# Nano_stepper.net
KiCad netlist of a schematic drawn in Altium Designer
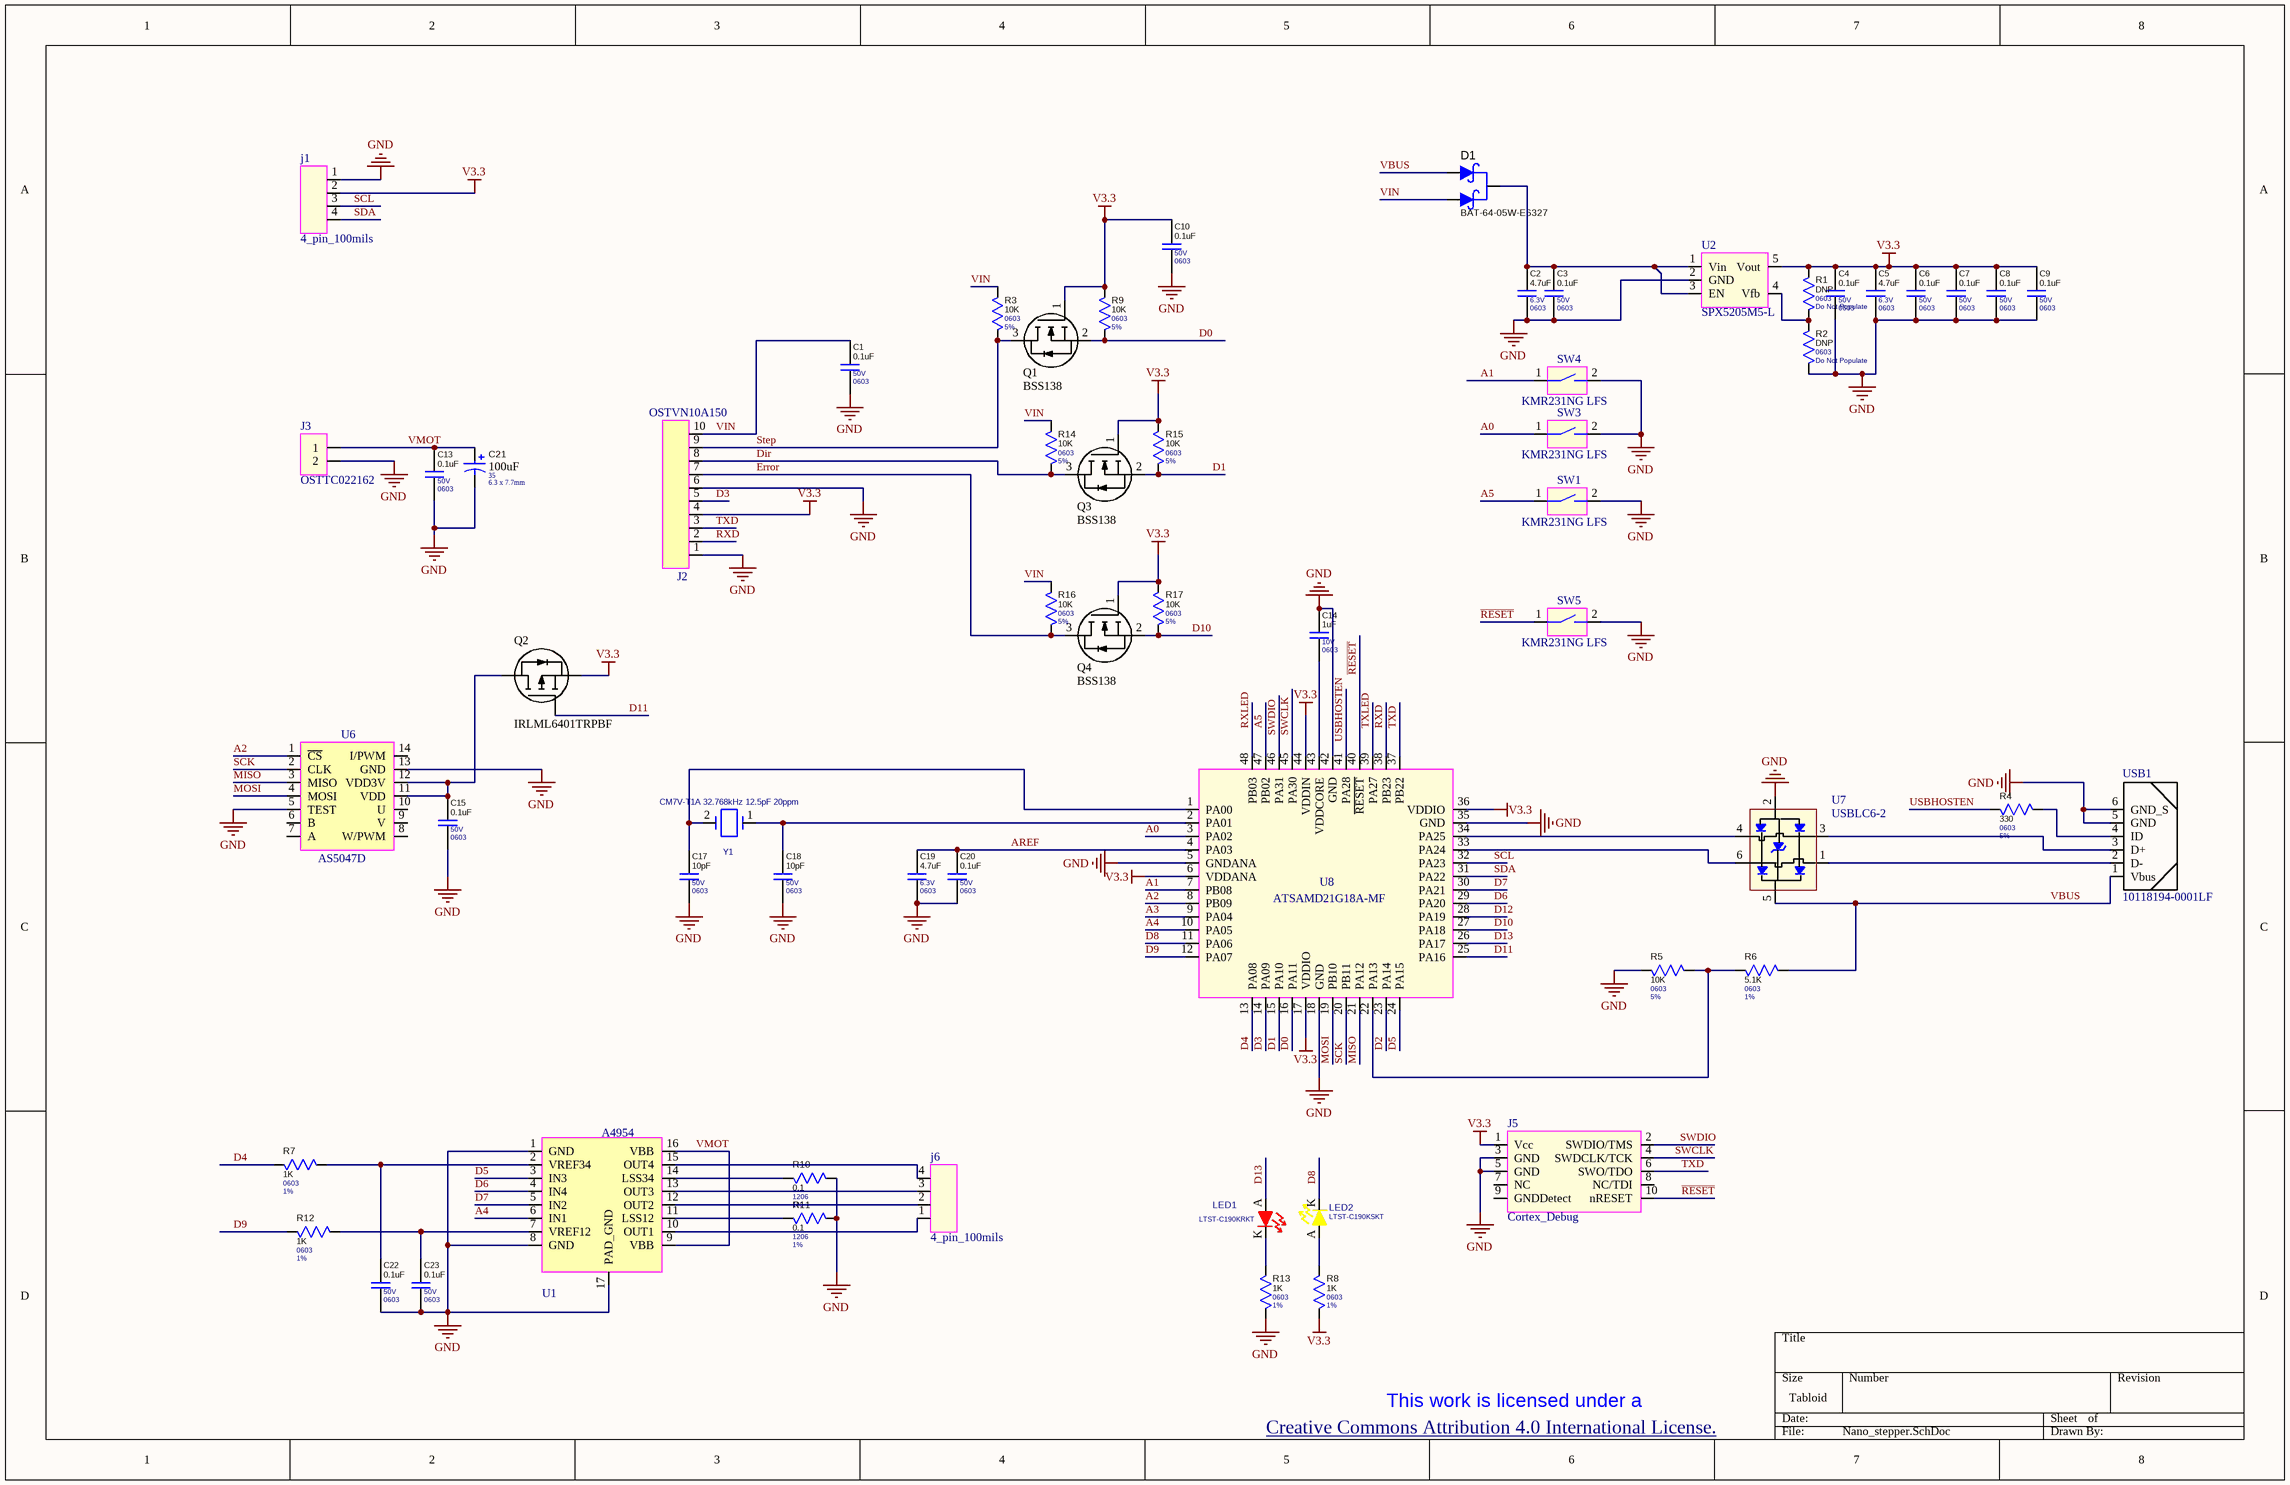
[diagram p0: Nano_stepper.SchDoc]

(export (version "E")
  (design (tool "Eeschema 10.0.6"))
  (components
    (comp (ref "C1")
      (value "0.1uF")
      (footprint "CAP_0603_H")
      (description "CAP CER 0.1UF 50V Y5V 0603")
      (fields
        (field (name "SIZE_IMPERIAL") "0603")
        (field (name "VOLTAGE_STR") "50V")
        (field (name "VOLTAGE") "50")
        (field (name "TOLERANCE") "-20%, +80%")
      )
      (libsource (lib "Misfit_library") (part "Cap"))
    )
    (comp (ref "C2")
      (value "4.7uF")
      (footprint "CAP_0603_H")
      (description "CAP 0603 CER 4.7UF 6.3V X5R 10%")
      (fields
        (field (name "SIZE_IMPERIAL") "0603")
        (field (name "VOLTAGE_STR") "6.3V")
        (field (name "VOLTAGE") "6.3")
        (field (name "TOLERANCE") "10%")
      )
      (libsource (lib "Misfit_library") (part "Cap"))
    )
    (comp (ref "C3")
      (value "0.1uF")
      (footprint "CAP_0603_H")
      (description "CAP CER 0.1UF 50V Y5V 0603")
      (fields
        (field (name "SIZE_IMPERIAL") "0603")
        (field (name "VOLTAGE_STR") "50V")
        (field (name "VOLTAGE") "50")
        (field (name "TOLERANCE") "-20%, +80%")
      )
      (libsource (lib "Misfit_library") (part "Cap"))
    )
    (comp (ref "C4")
      (value "0.1uF")
      (footprint "CAP_0603_H")
      (description "CAP CER 0.1UF 50V Y5V 0603")
      (fields
        (field (name "SIZE_IMPERIAL") "0603")
        (field (name "VOLTAGE_STR") "50V")
        (field (name "VOLTAGE") "50")
        (field (name "TOLERANCE") "-20%, +80%")
      )
      (libsource (lib "Misfit_library") (part "Cap"))
    )
    (comp (ref "C5")
      (value "4.7uF")
      (footprint "CAP_0603_H")
      (description "CAP 0603 CER 4.7UF 6.3V X5R 10%")
      (fields
        (field (name "SIZE_IMPERIAL") "0603")
        (field (name "VOLTAGE_STR") "6.3V")
        (field (name "VOLTAGE") "6.3")
        (field (name "TOLERANCE") "10%")
      )
      (libsource (lib "Misfit_library") (part "Cap"))
    )
    (comp (ref "C6")
      (value "0.1uF")
      (footprint "CAP_0603_H")
      (description "CAP CER 0.1UF 50V Y5V 0603")
      (fields
        (field (name "SIZE_IMPERIAL") "0603")
        (field (name "VOLTAGE_STR") "50V")
        (field (name "VOLTAGE") "50")
        (field (name "TOLERANCE") "-20%, +80%")
      )
      (libsource (lib "Misfit_library") (part "Cap"))
    )
    (comp (ref "C7")
      (value "0.1uF")
      (footprint "CAP_0603_H")
      (description "CAP CER 0.1UF 50V Y5V 0603")
      (fields
        (field (name "SIZE_IMPERIAL") "0603")
        (field (name "VOLTAGE_STR") "50V")
        (field (name "VOLTAGE") "50")
        (field (name "TOLERANCE") "-20%, +80%")
      )
      (libsource (lib "Misfit_library") (part "Cap"))
    )
    (comp (ref "C8")
      (value "0.1uF")
      (footprint "CAP_0603_H")
      (description "CAP CER 0.1UF 50V Y5V 0603")
      (fields
        (field (name "SIZE_IMPERIAL") "0603")
        (field (name "VOLTAGE_STR") "50V")
        (field (name "VOLTAGE") "50")
        (field (name "TOLERANCE") "-20%, +80%")
      )
      (libsource (lib "Misfit_library") (part "Cap"))
    )
    (comp (ref "C9")
      (value "0.1uF")
      (footprint "CAP_0603_H")
      (description "CAP CER 0.1UF 50V Y5V 0603")
      (fields
        (field (name "SIZE_IMPERIAL") "0603")
        (field (name "VOLTAGE_STR") "50V")
        (field (name "VOLTAGE") "50")
        (field (name "TOLERANCE") "-20%, +80%")
      )
      (libsource (lib "Misfit_library") (part "Cap"))
    )
    (comp (ref "C10")
      (value "0.1uF")
      (footprint "CAP_0603_H")
      (description "CAP CER 0.1UF 50V Y5V 0603")
      (fields
        (field (name "SIZE_IMPERIAL") "0603")
        (field (name "VOLTAGE_STR") "50V")
        (field (name "VOLTAGE") "50")
        (field (name "TOLERANCE") "-20%, +80%")
      )
      (libsource (lib "Misfit_library") (part "Cap"))
    )
    (comp (ref "C13")
      (value "0.1uF")
      (footprint "CAP_0603_H")
      (description "CAP CER 0.1UF 50V Y5V 0603")
      (fields
        (field (name "SIZE_IMPERIAL") "0603")
        (field (name "VOLTAGE_STR") "50V")
        (field (name "VOLTAGE") "50")
        (field (name "TOLERANCE") "-20%, +80%")
      )
      (libsource (lib "Misfit_library") (part "Cap"))
    )
    (comp (ref "C14")
      (value "1uF")
      (footprint "CAP_0603_H")
      (description "CAP 0603 CER 1UF 10V X5R 10%")
      (fields
        (field (name "SIZE_IMPERIAL") "0603")
        (field (name "VOLTAGE_STR") "10V")
        (field (name "VOLTAGE") "10")
        (field (name "TOLERANCE") "10 %")
      )
      (libsource (lib "Misfit_library") (part "Cap"))
    )
    (comp (ref "C15")
      (value "0.1uF")
      (footprint "CAP_0603_H")
      (description "CAP CER 0.1UF 50V Y5V 0603")
      (fields
        (field (name "SIZE_IMPERIAL") "0603")
        (field (name "VOLTAGE_STR") "50V")
        (field (name "VOLTAGE") "50")
        (field (name "TOLERANCE") "-20%, +80%")
      )
      (libsource (lib "Misfit_library") (part "Cap"))
    )
    (comp (ref "C17")
      (value "10pF")
      (footprint "CAP_0603_H")
      (description "CAP 0603 CER 10PF 50V C0G 5%")
      (fields
        (field (name "SIZE_IMPERIAL") "0603")
        (field (name "VOLTAGE_STR") "50V")
        (field (name "VOLTAGE") "50")
        (field (name "TOLERANCE") "5 %")
      )
      (libsource (lib "Misfit_library") (part "Cap"))
    )
    (comp (ref "C18")
      (value "10pF")
      (footprint "CAP_0603_H")
      (description "CAP 0603 CER 10PF 50V C0G 5%")
      (fields
        (field (name "SIZE_IMPERIAL") "0603")
        (field (name "VOLTAGE_STR") "50V")
        (field (name "VOLTAGE") "50")
        (field (name "TOLERANCE") "5 %")
      )
      (libsource (lib "Misfit_library") (part "Cap"))
    )
    (comp (ref "C19")
      (value "4.7uF")
      (footprint "CAP_0603_H")
      (description "CAP 0603 CER 4.7UF 6.3V X5R 10%")
      (fields
        (field (name "SIZE_IMPERIAL") "0603")
        (field (name "VOLTAGE_STR") "6.3V")
        (field (name "VOLTAGE") "6.3")
        (field (name "TOLERANCE") "10%")
      )
      (libsource (lib "Misfit_library") (part "Cap"))
    )
    (comp (ref "C20")
      (value "0.1uF")
      (footprint "CAP_0603_H")
      (description "CAP CER 0.1UF 50V Y5V 0603")
      (fields
        (field (name "SIZE_IMPERIAL") "0603")
        (field (name "VOLTAGE_STR") "50V")
        (field (name "VOLTAGE") "50")
        (field (name "TOLERANCE") "-20%, +80%")
      )
      (libsource (lib "Misfit_library") (part "Cap"))
    )
    (comp (ref "C21")
      (value "100uF")
      (footprint "UWT1V101MCL1GS")
      (description "100uF 35V SMD")
      (fields
        (field (name "SIZE") "6.3 x 7.7mm")
        (field (name "VOLTAGE") "35")
        (field (name "TOLERANCE") "20%")
        (field (name "MANUFACTURER_PART_NUMBER") "UWT1V101MCL1GS")
      )
      (libsource (lib "Misfit_library") (part "CAP_POL"))
    )
    (comp (ref "C22")
      (value "0.1uF")
      (footprint "CAP_0603_H")
      (description "CAP CER 0.1UF 50V Y5V 0603")
      (fields
        (field (name "SIZE_IMPERIAL") "0603")
        (field (name "VOLTAGE_STR") "50V")
        (field (name "VOLTAGE") "50")
        (field (name "TOLERANCE") "-20%, +80%")
      )
      (libsource (lib "Misfit_library") (part "Cap"))
    )
    (comp (ref "C23")
      (value "0.1uF")
      (footprint "CAP_0603_H")
      (description "CAP CER 0.1UF 50V Y5V 0603")
      (fields
        (field (name "SIZE_IMPERIAL") "0603")
        (field (name "VOLTAGE_STR") "50V")
        (field (name "VOLTAGE") "50")
        (field (name "TOLERANCE") "-20%, +80%")
      )
      (libsource (lib "Misfit_library") (part "Cap"))
    )
    (comp (ref "D1")
      (value "BAT-64-05W-E6327")
      (footprint "BAT-64-05W-E6327")
      (description "DIODE SCHOTTKY 40V SOT-323 250mA")
      (fields
        (field (name "MANUFACTURER_PART_NUMBER") "BAT 64-05W H6327")
        (field (name "MANUFACTURER") "Infineon Technologies")
      )
      (libsource (lib "Misfit_library") (part "BAT-64-05W-E6327"))
    )
    (comp (ref "j1")
      (value "4_pin_100mils")
      (footprint "4_pin_100mils")
      (fields (field (name "MANUFACTURER") "none") (field (name "VOLTAGE") "0"))
      (libsource (lib "Misfit_library") (part "4_pin_100mils"))
    )
    (comp (ref "J2")
      (value "OSTVN10A150")
      (footprint "OSTVN10A150")
      (description "CONN TERM BLOCK 2.54MM 10POS PCB")
      (fields
        (field (name "MANUFACTURER") "On Shore Technology Inc.")
        (field (name "VENDOR_PART_NUMBER") "ED10567-ND")
      )
      (libsource (lib "Misfit_library") (part "OSTVN10A150"))
    )
    (comp (ref "J3")
      (value "OSTTC022162")
      (footprint "OSTTC022162")
      (description "TERM BLOCK 5.08MM VERT 2POS PCB")
      (fields
        (field (name "MANUFACTURER") "On Shore Technology Inc")
        (field (name "VENDOR_PART_NUMBER") "ED2609-ND")
      )
      (libsource (lib "Misfit_library") (part "OSTTC022162"))
    )
    (comp (ref "J5")
      (value "Cortex_Debug")
      (footprint "FTSH-105-01-L-D")
      (description "CONN HEADER 10POS DUAL .05&quot; T/H")
      (fields
        (field (name "MANUFACTURER_PART_NUMBER") "FTSH-105-01-L-D")
        (field (name "MANUFACTURER") "Samtec Inc")
      )
      (libsource (lib "Misfit_library") (part "Cortex_Debug"))
    )
    (comp (ref "j6")
      (value "4_pin_100mils")
      (footprint "4_pin_100mils")
      (fields (field (name "MANUFACTURER") "none") (field (name "VOLTAGE") "0"))
      (libsource (lib "") (part "4_pin_100mils_1"))
    )
    (comp (ref "LED1")
      (value "LTST-C190KRKT")
      (footprint "LTST-C190KRKT")
      (description "LED SUPER RED CLEAR 0603 SMD 20mA Vf=2V")
      (fields (field (name "MANUFACTURER") "Lite-On Inc") (field (name "VENDOR_PART_NUMBER") "160-1436-1-ND"))
      (libsource (lib "Misfit_library") (part "RED_LED"))
    )
    (comp (ref "LED2")
      (value "LTST-C190KSKT")
      (footprint "LTST-C190KSKT")
      (description "LED YELLOW CLEAR 0603 SMD")
      (fields (field (name "MANUFACTURER") "Lite-On Inc") (field (name "VENDOR_PART_NUMBER") "160-1437-6-ND"))
      (libsource (lib "Misfit_library") (part "LTST-C190KSKT"))
    )
    (comp (ref "Q1")
      (value "BSS138")
      (footprint "BSS138")
      (fields (field (name "VOLTAGE") "0"))
      (libsource (lib "Misfit_library") (part "BSS138"))
    )
    (comp (ref "Q2")
      (value "IRLML6401TRPBF")
      (footprint "IRLML6401TRPBF_M")
      (description "MOSFET P-CH 12V 4.3A SOT-23")
      (fields
        (field (name "MANUFACTURER") "International Rectifier")
        (field (name "MISFIT PART NUMBER") "00013-209-00061")
      )
      (libsource (lib "Misfit_library") (part "IRLML6401TRPBF"))
    )
    (comp (ref "Q3")
      (value "BSS138")
      (footprint "BSS138")
      (fields (field (name "VOLTAGE") "0"))
      (libsource (lib "Misfit_library") (part "BSS138"))
    )
    (comp (ref "Q4")
      (value "BSS138")
      (footprint "BSS138")
      (fields (field (name "VOLTAGE") "0"))
      (libsource (lib "Misfit_library") (part "BSS138"))
    )
    (comp (ref "R1")
      (value "DNP")
      (footprint "RES_0603_H")
      (fields
        (field (name "SIZE_IMPERIAL") "0603")
        (field (name "TOLERANCE") "Do Not Populate")
        (field (name "MISFIT PART NUMBER") "00015-126-00006")
        (field (name "OLD PART NUMBER") "4530-0101-00")
        (field (name "VENDOR_PART_NUMBER") "P0.0GTR-ND")
      )
      (libsource (lib "Misfit_library") (part "resistor"))
    )
    (comp (ref "R2")
      (value "DNP")
      (footprint "RES_0603_H")
      (fields
        (field (name "SIZE_IMPERIAL") "0603")
        (field (name "TOLERANCE") "Do Not Populate")
        (field (name "MISFIT PART NUMBER") "00015-126-00006")
        (field (name "OLD PART NUMBER") "4530-0101-00")
        (field (name "VENDOR_PART_NUMBER") "P0.0GTR-ND")
      )
      (libsource (lib "Misfit_library") (part "resistor"))
    )
    (comp (ref "R3")
      (value "10K")
      (footprint "RES_0603_H")
      (description "RES 0603 TKF 10K 5% 1/10W")
      (fields
        (field (name "SIZE_IMPERIAL") "0603")
        (field (name "TOLERANCE") "5%")
        (field (name "MANUFACTURER_PART_NUMBER") "RC0603JR-0710KL")
        (field (name "MANUFACTURER") "Yageo")
      )
      (libsource (lib "Misfit_library") (part "resistor"))
    )
    (comp (ref "R4")
      (value "330")
      (footprint "RES_0603_H")
      (description "RES 0603 TKF 330R 5% 1/10W")
      (fields
        (field (name "SIZE_IMPERIAL") "0603")
        (field (name "TOLERANCE") "5%")
        (field (name "MANUFACTURER_PART_NUMBER") "RC0603JR-07330RL")
        (field (name "MANUFACTURER") "Yageo")
      )
      (libsource (lib "Misfit_library") (part "resistor"))
    )
    (comp (ref "R5")
      (value "10K")
      (footprint "RES_0603_H")
      (description "RES 0603 TKF 10K 5% 1/10W")
      (fields
        (field (name "SIZE_IMPERIAL") "0603")
        (field (name "TOLERANCE") "5%")
        (field (name "MANUFACTURER_PART_NUMBER") "RC0603JR-0710KL")
        (field (name "MANUFACTURER") "Yageo")
      )
      (libsource (lib "Misfit_library") (part "resistor"))
    )
    (comp (ref "R6")
      (value "5.1K")
      (footprint "RES_0603_H")
      (description "RES 0603 TKF 5.1K 1% 1/10W")
      (fields
        (field (name "SIZE_IMPERIAL") "0603")
        (field (name "TOLERANCE") "1%")
        (field (name "MANUFACTURER_PART_NUMBER") "CRCW06035K10FKEA")
        (field (name "MANUFACTURER") "Vishay/Dale")
      )
      (libsource (lib "Misfit_library") (part "resistor"))
    )
    (comp (ref "R7")
      (value "1K")
      (footprint "RES_0603_H")
      (description "RES 0603 TKF 1K 1% 1/10W")
      (fields
        (field (name "SIZE_IMPERIAL") "0603")
        (field (name "TOLERANCE") "1%")
        (field (name "MANUFACTURER_PART_NUMBER") "CRCW06031K00FKEAHP")
        (field (name "MANUFACTURER") "Vishay/Dale")
      )
      (libsource (lib "Misfit_library") (part "resistor"))
    )
    (comp (ref "R8")
      (value "1K")
      (footprint "RES_0603_H")
      (description "RES 0603 TKF 1K 1% 1/10W")
      (fields
        (field (name "SIZE_IMPERIAL") "0603")
        (field (name "TOLERANCE") "1%")
        (field (name "MANUFACTURER_PART_NUMBER") "CRCW06031K00FKEAHP")
        (field (name "MANUFACTURER") "Vishay/Dale")
      )
      (libsource (lib "Misfit_library") (part "resistor"))
    )
    (comp (ref "R9")
      (value "10K")
      (footprint "RES_0603_H")
      (description "RES 0603 TKF 10K 5% 1/10W")
      (fields
        (field (name "SIZE_IMPERIAL") "0603")
        (field (name "TOLERANCE") "5%")
        (field (name "MANUFACTURER_PART_NUMBER") "RC0603JR-0710KL")
        (field (name "MANUFACTURER") "Yageo")
      )
      (libsource (lib "Misfit_library") (part "resistor"))
    )
    (comp (ref "R10")
      (value "0.1")
      (footprint "RES_1206_H")
      (description "RES 0.2 OHM 0.25W 1% 1206 SMD")
      (fields
        (field (name "SIZE_IMPERIAL") "1206")
        (field (name "TOLERANCE") "1%")
        (field (name "MANUFACTURER_PART_NUMBER") "PT1206FR-070R2L")
        (field (name "MANUFACTURER") "Yageo")
      )
      (libsource (lib "Misfit_library") (part "resistor"))
    )
    (comp (ref "R11")
      (value "0.1")
      (footprint "RES_1206_H")
      (description "RES 0.2 OHM 0.25W 1% 1206 SMD")
      (fields
        (field (name "SIZE_IMPERIAL") "1206")
        (field (name "TOLERANCE") "1%")
        (field (name "MANUFACTURER_PART_NUMBER") "PT1206FR-070R2L")
        (field (name "MANUFACTURER") "Yageo")
      )
      (libsource (lib "Misfit_library") (part "resistor"))
    )
    (comp (ref "R12")
      (value "1K")
      (footprint "RES_0603_H")
      (description "RES 0603 TKF 1K 1% 1/10W")
      (fields
        (field (name "SIZE_IMPERIAL") "0603")
        (field (name "TOLERANCE") "1%")
        (field (name "MANUFACTURER_PART_NUMBER") "CRCW06031K00FKEAHP")
        (field (name "MANUFACTURER") "Vishay/Dale")
      )
      (libsource (lib "Misfit_library") (part "resistor"))
    )
    (comp (ref "R13")
      (value "1K")
      (footprint "RES_0603_H")
      (description "RES 0603 TKF 1K 1% 1/10W")
      (fields
        (field (name "SIZE_IMPERIAL") "0603")
        (field (name "TOLERANCE") "1%")
        (field (name "MANUFACTURER_PART_NUMBER") "CRCW06031K00FKEAHP")
        (field (name "MANUFACTURER") "Vishay/Dale")
      )
      (libsource (lib "Misfit_library") (part "resistor"))
    )
    (comp (ref "R14")
      (value "10K")
      (footprint "RES_0603_H")
      (description "RES 0603 TKF 10K 5% 1/10W")
      (fields
        (field (name "SIZE_IMPERIAL") "0603")
        (field (name "TOLERANCE") "5%")
        (field (name "MANUFACTURER_PART_NUMBER") "RC0603JR-0710KL")
        (field (name "MANUFACTURER") "Yageo")
      )
      (libsource (lib "Misfit_library") (part "resistor"))
    )
    (comp (ref "R15")
      (value "10K")
      (footprint "RES_0603_H")
      (description "RES 0603 TKF 10K 5% 1/10W")
      (fields
        (field (name "SIZE_IMPERIAL") "0603")
        (field (name "TOLERANCE") "5%")
        (field (name "MANUFACTURER_PART_NUMBER") "RC0603JR-0710KL")
        (field (name "MANUFACTURER") "Yageo")
      )
      (libsource (lib "Misfit_library") (part "resistor"))
    )
    (comp (ref "R16")
      (value "10K")
      (footprint "RES_0603_H")
      (description "RES 0603 TKF 10K 5% 1/10W")
      (fields
        (field (name "SIZE_IMPERIAL") "0603")
        (field (name "TOLERANCE") "5%")
        (field (name "MANUFACTURER_PART_NUMBER") "RC0603JR-0710KL")
        (field (name "MANUFACTURER") "Yageo")
      )
      (libsource (lib "Misfit_library") (part "resistor"))
    )
    (comp (ref "R17")
      (value "10K")
      (footprint "RES_0603_H")
      (description "RES 0603 TKF 10K 5% 1/10W")
      (fields
        (field (name "SIZE_IMPERIAL") "0603")
        (field (name "TOLERANCE") "5%")
        (field (name "MANUFACTURER_PART_NUMBER") "RC0603JR-0710KL")
        (field (name "MANUFACTURER") "Yageo")
      )
      (libsource (lib "Misfit_library") (part "resistor"))
    )
    (comp (ref "SW1")
      (value "KMR231NG LFS")
      (footprint "KMR231NG_LFS")
      (fields (field (name "VOLTAGE") "0"))
      (libsource (lib "Misfit_library") (part "KMR231NG_LFS"))
    )
    (comp (ref "SW3")
      (value "KMR231NG LFS")
      (footprint "KMR231NG_LFS")
      (fields (field (name "VOLTAGE") "0"))
      (libsource (lib "Misfit_library") (part "KMR231NG_LFS"))
    )
    (comp (ref "SW4")
      (value "KMR231NG LFS")
      (footprint "KMR231NG_LFS")
      (fields (field (name "VOLTAGE") "0"))
      (libsource (lib "Misfit_library") (part "KMR231NG_LFS"))
    )
    (comp (ref "SW5")
      (value "KMR231NG LFS")
      (footprint "KMR231NG_LFS")
      (fields (field (name "VOLTAGE") "0"))
      (libsource (lib "Misfit_library") (part "KMR231NG_LFS"))
    )
    (comp (ref "U1")
      (value "A4954")
      (footprint "A4954")
      (fields (field (name "VOLTAGE") "0"))
      (libsource (lib "Misfit_library") (part "A4954"))
    )
    (comp (ref "U2")
      (value "SPX5205M5-L")
      (footprint "SPX5205M5-L")
      (description "IC REG LDO ADJ 150MA LN SOT23-5")
      (fields
        (field (name "MANUFACTURER") "Exar Corporation")
        (field (name "MISFIT PART NUMBER") "00012-001-42775")
      )
      (libsource (lib "Misfit_library") (part "SPX5205M5-L"))
    )
    (comp (ref "U6")
      (value "AS5047D")
      (footprint "AS5047D")
      (fields (field (name "VOLTAGE") "0"))
      (libsource (lib "Misfit_library") (part "AS5047D"))
    )
    (comp (ref "U7")
      (value "USBLC6-2")
      (footprint "USBLC6-2SC6")
      (description "TVS Diode Arrays ESD Protection Low Cap")
      (fields
        (field (name "MANUFACTURER_PART_NUMBER") "USBLC6-2SC6")
        (field (name "MANUFACTURER") "STMicroelectronics")
      )
      (libsource (lib "Misfit_library") (part "USBLC6-2SC6"))
    )
    (comp (ref "U8")
      (value "ATSAMD21G18A-MF")
      (footprint "ATSAMD21G18A-MF")
      (libsource (lib "Misfit_library") (part "ATSAMD21G18A-MF"))
    )
    (comp (ref "USB1")
      (value "10118194-0001LF")
      (footprint "10118194-0001LF")
      (description "Connector Receptacle USB - micro B 2.0 5 Position Surface Mount, Right Angle, Horizontal")
      (fields (field (name "MANUFACTURER") "FCI") (field (name "VENDOR_PART_NUMBER") "609-4618-6-ND"))
      (libsource (lib "Misfit_library") (part "10118194-0001LF"))
    )
    (comp (ref "Y1")
      (value "CM7V-T1A 32.768kHz 12.5pF 20ppm")
      (footprint "FC-135-32.7680KA-A3")
      (description "CRYSTAL 32.7680KHZ 12.5PF SMD")
      (fields
        (field (name "MANUFACTURER") "Micro Crystal")
        (field (name "MISFIT PART NUMBER") "00012-001-47041")
      )
      (libsource (lib "Misfit_library") (part "CRYSTAL"))
    )
  )
  (nets
    (net (code "1") (name "/A0") (class "Default")
      (node (ref "SW3") (pin "1") (pintype "passive"))
      (node (ref "U8") (pin "3") (pinfunction "PA02_3") (pintype "passive"))
    )
    (net (code "2") (name "/A1") (class "Default")
      (node (ref "SW4") (pin "1") (pintype "passive"))
      (node (ref "U8") (pin "7") (pinfunction "PB08_7") (pintype "passive"))
    )
    (net (code "3") (name "/A2") (class "Default")
      (node (ref "U6") (pin "1") (pinfunction "CS_1") (pintype "passive"))
      (node (ref "U8") (pin "8") (pinfunction "PB09_8") (pintype "passive"))
    )
    (net (code "4") (name "/A3") (class "Default")
      (node (ref "U8") (pin "9") (pinfunction "PA04_9") (pintype "passive"))
    )
    (net (code "5") (name "/A4") (class "Default")
      (node (ref "U1") (pin "6") (pinfunction "IN1_6") (pintype "passive"))
      (node (ref "U8") (pin "10") (pinfunction "PA05_10") (pintype "passive"))
    )
    (net (code "6") (name "/A5") (class "Default")
      (node (ref "SW1") (pin "1") (pintype "passive"))
      (node (ref "U8") (pin "47") (pinfunction "PB02_47") (pintype "passive"))
    )
    (net (code "7") (name "/AREF") (class "Default")
      (node (ref "C19") (pin "1") (pintype "passive"))
      (node (ref "C20") (pin "1") (pintype "passive"))
      (node (ref "U8") (pin "4") (pinfunction "PA03_4") (pintype "passive"))
    )
    (net (code "8") (name "/D0") (class "Default")
      (node (ref "Q1") (pin "2") (pintype "passive"))
      (node (ref "R9") (pin "1") (pintype "passive"))
      (node (ref "U8") (pin "16") (pinfunction "PA11_16") (pintype "passive"))
    )
    (net (code "9") (name "/D1") (class "Default")
      (node (ref "Q3") (pin "2") (pintype "passive"))
      (node (ref "R15") (pin "1") (pintype "passive"))
      (node (ref "U8") (pin "15") (pinfunction "PA10_15") (pintype "passive"))
    )
    (net (code "10") (name "/D2") (class "Default")
      (node (ref "U8") (pin "23") (pinfunction "PA14_23") (pintype "passive"))
    )
    (net (code "11") (name "/D3") (class "Default")
      (node (ref "J2") (pin "5") (pintype "passive"))
      (node (ref "U8") (pin "14") (pinfunction "PA09_14") (pintype "passive"))
    )
    (net (code "12") (name "/D4") (class "Default")
      (node (ref "R7") (pin "1") (pintype "passive"))
      (node (ref "U8") (pin "13") (pinfunction "PA08_13") (pintype "passive"))
    )
    (net (code "13") (name "/D5") (class "Default")
      (node (ref "U1") (pin "3") (pinfunction "IN3_3") (pintype "passive"))
      (node (ref "U8") (pin "24") (pinfunction "PA15_24") (pintype "passive"))
    )
    (net (code "14") (name "/D6") (class "Default")
      (node (ref "U1") (pin "4") (pinfunction "IN4_4") (pintype "passive"))
      (node (ref "U8") (pin "29") (pinfunction "PA20_29") (pintype "passive"))
    )
    (net (code "15") (name "/D7") (class "Default")
      (node (ref "U1") (pin "5") (pinfunction "IN2_5") (pintype "passive"))
      (node (ref "U8") (pin "30") (pinfunction "PA21_30") (pintype "passive"))
    )
    (net (code "16") (name "/D8") (class "Default")
      (node (ref "LED2") (pin "K") (pinfunction "K_K") (pintype "passive"))
      (node (ref "U8") (pin "11") (pinfunction "PA06_11") (pintype "passive"))
    )
    (net (code "17") (name "/D9") (class "Default")
      (node (ref "R12") (pin "1") (pintype "passive"))
      (node (ref "U8") (pin "12") (pinfunction "PA07_12") (pintype "passive"))
    )
    (net (code "18") (name "/D10") (class "Default")
      (node (ref "Q4") (pin "2") (pintype "passive"))
      (node (ref "R17") (pin "1") (pintype "passive"))
      (node (ref "U8") (pin "27") (pinfunction "PA18_27") (pintype "passive"))
    )
    (net (code "19") (name "/D11") (class "Default")
      (node (ref "Q2") (pin "1") (pintype "passive"))
      (node (ref "U8") (pin "25") (pinfunction "PA16_25") (pintype "passive"))
    )
    (net (code "20") (name "/D12") (class "Default")
      (node (ref "U8") (pin "28") (pinfunction "PA19_28") (pintype "passive"))
    )
    (net (code "21") (name "/D13") (class "Default")
      (node (ref "LED1") (pin "A") (pinfunction "A_A") (pintype "passive"))
      (node (ref "U8") (pin "26") (pinfunction "PA17_26") (pintype "passive"))
    )
    (net (code "22") (name "/Dir") (class "Default")
      (node (ref "J2") (pin "8") (pintype "passive"))
      (node (ref "Q3") (pin "3") (pintype "passive"))
      (node (ref "R14") (pin "1") (pintype "passive"))
    )
    (net (code "23") (name "/Error") (class "Default")
      (node (ref "J2") (pin "7") (pintype "passive"))
      (node (ref "Q4") (pin "3") (pintype "passive"))
      (node (ref "R16") (pin "1") (pintype "passive"))
    )
    (net (code "24") (name "/MISO") (class "Default")
      (node (ref "U6") (pin "3") (pinfunction "MISO_3") (pintype "passive"))
      (node (ref "U8") (pin "21") (pinfunction "PA12_21") (pintype "passive"))
    )
    (net (code "25") (name "/MOSI") (class "Default")
      (node (ref "U6") (pin "4") (pinfunction "MOSI_4") (pintype "passive"))
      (node (ref "U8") (pin "19") (pinfunction "PB10_19") (pintype "passive"))
    )
    (net (code "26") (name "/RESET") (class "Default")
      (node (ref "J5") (pin "10") (pinfunction "nRESET_10") (pintype "passive"))
      (node (ref "SW5") (pin "1") (pintype "passive"))
      (node (ref "U8") (pin "40") (pinfunction "RESET_40") (pintype "passive"))
    )
    (net (code "27") (name "/RXD") (class "Default")
      (node (ref "J2") (pin "2") (pintype "passive"))
      (node (ref "U8") (pin "38") (pinfunction "PB23_38") (pintype "passive"))
    )
    (net (code "28") (name "/RXLED") (class "Default")
      (node (ref "U8") (pin "48") (pinfunction "PB03_48") (pintype "passive"))
    )
    (net (code "29") (name "/SCK") (class "Default")
      (node (ref "U6") (pin "2") (pinfunction "CLK_2") (pintype "passive"))
      (node (ref "U8") (pin "20") (pinfunction "PB11_20") (pintype "passive"))
    )
    (net (code "30") (name "/SCL") (class "Default")
      (node (ref "U8") (pin "32") (pinfunction "PA23_32") (pintype "passive"))
      (node (ref "j1") (pin "3") (pinfunction "3_3") (pintype "passive"))
    )
    (net (code "31") (name "/SDA") (class "Default")
      (node (ref "U8") (pin "31") (pinfunction "PA22_31") (pintype "passive"))
      (node (ref "j1") (pin "4") (pinfunction "4_4") (pintype "passive"))
    )
    (net (code "32") (name "/SWCLK") (class "Default")
      (node (ref "J5") (pin "4") (pinfunction "SWDCLK/TCK_4") (pintype "passive"))
      (node (ref "U8") (pin "45") (pinfunction "PA30_45") (pintype "passive"))
    )
    (net (code "33") (name "/SWDIO") (class "Default")
      (node (ref "J5") (pin "2") (pinfunction "SWDIO/TMS_2") (pintype "passive"))
      (node (ref "U8") (pin "46") (pinfunction "PA31_46") (pintype "passive"))
    )
    (net (code "34") (name "/Step") (class "Default")
      (node (ref "J2") (pin "9") (pintype "passive"))
      (node (ref "Q1") (pin "3") (pintype "passive"))
      (node (ref "R3") (pin "1") (pintype "passive"))
    )
    (net (code "35") (name "/TXD") (class "Default")
      (node (ref "J2") (pin "3") (pintype "passive"))
      (node (ref "J5") (pin "6") (pinfunction "SWO/TDO_6") (pintype "passive"))
      (node (ref "U8") (pin "37") (pinfunction "PB22_37") (pintype "passive"))
    )
    (net (code "36") (name "/TXLED") (class "Default")
      (node (ref "U8") (pin "39") (pinfunction "PA27_39") (pintype "passive"))
    )
    (net (code "37") (name "/USBHOSTEN") (class "Default")
      (node (ref "R4") (pin "1") (pintype "passive"))
      (node (ref "U8") (pin "41") (pinfunction "PA28_41") (pintype "passive"))
    )
    (net (code "38") (name "/VBUS") (class "Default")
      (node (ref "D1") (pin "1") (pintype "passive"))
      (node (ref "R6") (pin "2") (pintype "passive"))
      (node (ref "U7") (pin "5") (pinfunction "VBUS_5") (pintype "passive"))
      (node (ref "USB1") (pin "1") (pinfunction "Vbus_1") (pintype "passive"))
    )
    (net (code "39") (name "/VIN") (class "Default")
      (node (ref "C1") (pin "1") (pintype "passive"))
      (node (ref "D1") (pin "2") (pintype "passive"))
      (node (ref "J2") (pin "10") (pintype "passive"))
      (node (ref "R14") (pin "2") (pintype "passive"))
      (node (ref "R16") (pin "2") (pintype "passive"))
      (node (ref "R3") (pin "2") (pintype "passive"))
    )
    (net (code "40") (name "/VMOT") (class "Default")
      (node (ref "C13") (pin "1") (pintype "passive"))
      (node (ref "C21") (pin "1") (pinfunction "Pos_1") (pintype "passive"))
      (node (ref "J3") (pin "1") (pinfunction "1_1") (pintype "passive"))
      (node (ref "U1") (pin "16") (pinfunction "VBB_16") (pintype "passive"))
      (node (ref "U1") (pin "9") (pinfunction "VBB_9") (pintype "passive"))
    )
    (net (code "41") (name "GND") (class "Default")
      (node (ref "C1") (pin "2") (pintype "passive"))
      (node (ref "C10") (pin "2") (pintype "passive"))
      (node (ref "C13") (pin "2") (pintype "passive"))
      (node (ref "C14") (pin "1") (pintype "passive"))
      (node (ref "C15") (pin "2") (pintype "passive"))
      (node (ref "C17") (pin "2") (pintype "passive"))
      (node (ref "C18") (pin "2") (pintype "passive"))
      (node (ref "C19") (pin "2") (pintype "passive"))
      (node (ref "C2") (pin "2") (pintype "passive"))
      (node (ref "C20") (pin "2") (pintype "passive"))
      (node (ref "C21") (pin "2") (pinfunction "Neg_2") (pintype "passive"))
      (node (ref "C22") (pin "2") (pintype "passive"))
      (node (ref "C23") (pin "2") (pintype "passive"))
      (node (ref "C3") (pin "2") (pintype "passive"))
      (node (ref "C4") (pin "2") (pintype "passive"))
      (node (ref "C5") (pin "2") (pintype "passive"))
      (node (ref "C6") (pin "2") (pintype "passive"))
      (node (ref "C7") (pin "2") (pintype "passive"))
      (node (ref "C8") (pin "2") (pintype "passive"))
      (node (ref "C9") (pin "2") (pintype "passive"))
      (node (ref "J2") (pin "1") (pintype "passive"))
      (node (ref "J2") (pin "6") (pintype "passive"))
      (node (ref "J3") (pin "2") (pinfunction "2_2") (pintype "passive"))
      (node (ref "J5") (pin "3") (pinfunction "GND_3") (pintype "passive"))
      (node (ref "J5") (pin "5") (pinfunction "GND_5") (pintype "passive"))
      (node (ref "R10") (pin "2") (pintype "passive"))
      (node (ref "R11") (pin "2") (pintype "passive"))
      (node (ref "R13") (pin "2") (pintype "passive"))
      (node (ref "R2") (pin "1") (pintype "passive"))
      (node (ref "R5") (pin "1") (pintype "passive"))
      (node (ref "SW1") (pin "2") (pintype "passive"))
      (node (ref "SW3") (pin "2") (pintype "passive"))
      (node (ref "SW4") (pin "2") (pintype "passive"))
      (node (ref "SW5") (pin "2") (pintype "passive"))
      (node (ref "U1") (pin "1") (pinfunction "GND_1") (pintype "passive"))
      (node (ref "U1") (pin "17") (pinfunction "PAD_GND_17") (pintype "passive"))
      (node (ref "U1") (pin "8") (pinfunction "GND_8") (pintype "passive"))
      (node (ref "U2") (pin "2") (pinfunction "GND_2") (pintype "passive"))
      (node (ref "U6") (pin "13") (pinfunction "GND_13") (pintype "passive"))
      (node (ref "U6") (pin "5") (pinfunction "TEST_5") (pintype "passive"))
      (node (ref "U7") (pin "2") (pinfunction "GND_2") (pintype "passive"))
      (node (ref "U8") (pin "18") (pinfunction "GND_18") (pintype "passive"))
      (node (ref "U8") (pin "35") (pinfunction "GND_35") (pintype "passive"))
      (node (ref "U8") (pin "42") (pinfunction "GND_42") (pintype "passive"))
      (node (ref "U8") (pin "5") (pinfunction "GNDANA_5") (pintype "passive"))
      (node (ref "USB1") (pin "5") (pinfunction "GND_5") (pintype "passive"))
      (node (ref "USB1") (pin "6") (pinfunction "GND_S_6") (pintype "passive"))
      (node (ref "j1") (pin "1") (pinfunction "1_1") (pintype "passive"))
    )
    (net (code "42") (name "Net-(LED1-PadK)") (class "Default")
      (node (ref "LED1") (pin "K") (pinfunction "K_K") (pintype "passive"))
      (node (ref "R13") (pin "1") (pintype "passive"))
    )
    (net (code "43") (name "Net-(LED2-PadA)") (class "Default")
      (node (ref "LED2") (pin "A") (pinfunction "A_A") (pintype "passive"))
      (node (ref "R8") (pin "1") (pintype "passive"))
    )
    (net (code "44") (name "Net-(U1-LSS12)") (class "Default")
      (node (ref "R11") (pin "1") (pintype "passive"))
      (node (ref "U1") (pin "11") (pinfunction "LSS12_11") (pintype "passive"))
    )
    (net (code "45") (name "Net-(U1-LSS34)") (class "Default")
      (node (ref "R10") (pin "1") (pintype "passive"))
      (node (ref "U1") (pin "14") (pinfunction "LSS34_14") (pintype "passive"))
    )
    (net (code "46") (name "Net-(U1-OUT1)") (class "Default")
      (node (ref "U1") (pin "10") (pinfunction "OUT1_10") (pintype "passive"))
      (node (ref "j6") (pin "1") (pinfunction "1_1") (pintype "passive"))
    )
    (net (code "47") (name "Net-(U1-OUT2)") (class "Default")
      (node (ref "U1") (pin "12") (pinfunction "OUT2_12") (pintype "passive"))
      (node (ref "j6") (pin "2") (pinfunction "2_2") (pintype "passive"))
    )
    (net (code "48") (name "Net-(U1-OUT3)") (class "Default")
      (node (ref "U1") (pin "13") (pinfunction "OUT3_13") (pintype "passive"))
      (node (ref "j6") (pin "3") (pinfunction "3_3") (pintype "passive"))
    )
    (net (code "49") (name "Net-(U1-OUT4)") (class "Default")
      (node (ref "U1") (pin "15") (pinfunction "OUT4_15") (pintype "passive"))
      (node (ref "j6") (pin "4") (pinfunction "4_4") (pintype "passive"))
    )
    (net (code "50") (name "Net-(U1-VREF12)") (class "Default")
      (node (ref "C23") (pin "1") (pintype "passive"))
      (node (ref "R12") (pin "2") (pintype "passive"))
      (node (ref "U1") (pin "7") (pinfunction "VREF12_7") (pintype "passive"))
    )
    (net (code "51") (name "Net-(U1-VREF34)") (class "Default")
      (node (ref "C22") (pin "1") (pintype "passive"))
      (node (ref "R7") (pin "2") (pintype "passive"))
      (node (ref "U1") (pin "2") (pinfunction "VREF34_2") (pintype "passive"))
    )
    (net (code "52") (name "Net-(U2-EN)") (class "Default")
      (node (ref "C2") (pin "1") (pintype "passive"))
      (node (ref "C3") (pin "1") (pintype "passive"))
      (node (ref "D1") (pin "3") (pintype "passive"))
      (node (ref "U2") (pin "1") (pinfunction "Vin_1") (pintype "passive"))
      (node (ref "U2") (pin "3") (pinfunction "EN_3") (pintype "passive"))
    )
    (net (code "53") (name "Net-(U2-Vfb)") (class "Default")
      (node (ref "R1") (pin "1") (pintype "passive"))
      (node (ref "R2") (pin "2") (pintype "passive"))
      (node (ref "U2") (pin "4") (pinfunction "Vfb_4") (pintype "passive"))
    )
    (net (code "54") (name "Net-(U6-VDD)") (class "Default")
      (node (ref "C15") (pin "1") (pintype "passive"))
      (node (ref "Q2") (pin "3") (pintype "passive"))
      (node (ref "U6") (pin "11") (pinfunction "VDD_11") (pintype "passive"))
      (node (ref "U6") (pin "12") (pinfunction "VDD3V_12") (pintype "passive"))
    )
    (net (code "55") (name "Net-(U8-PA00)") (class "Default")
      (node (ref "C17") (pin "1") (pintype "passive"))
      (node (ref "U8") (pin "1") (pinfunction "PA00_1") (pintype "passive"))
      (node (ref "Y1") (pin "2") (pinfunction "B_2") (pintype "passive"))
    )
    (net (code "56") (name "Net-(U8-PA01)") (class "Default")
      (node (ref "C18") (pin "1") (pintype "passive"))
      (node (ref "U8") (pin "2") (pinfunction "PA01_2") (pintype "passive"))
      (node (ref "Y1") (pin "1") (pinfunction "A_1") (pintype "passive"))
    )
    (net (code "57") (name "Net-(U8-PA13)") (class "Default")
      (node (ref "R5") (pin "2") (pintype "passive"))
      (node (ref "R6") (pin "1") (pintype "passive"))
      (node (ref "U8") (pin "22") (pinfunction "PA13_22") (pintype "passive"))
    )
    (net (code "58") (name "Net-(U8-PA24)") (class "Default")
      (node (ref "U7") (pin "6") (pinfunction "IO1_6") (pintype "passive"))
      (node (ref "U8") (pin "33") (pinfunction "PA24_33") (pintype "passive"))
    )
    (net (code "59") (name "Net-(U8-PA25)") (class "Default")
      (node (ref "U7") (pin "4") (pinfunction "IO2_4") (pintype "passive"))
      (node (ref "U8") (pin "34") (pinfunction "PA25_34") (pintype "passive"))
    )
    (net (code "60") (name "Net-(U8-VDDCORE)") (class "Default")
      (node (ref "C14") (pin "2") (pintype "passive"))
      (node (ref "U8") (pin "43") (pinfunction "VDDCORE_43") (pintype "passive"))
    )
    (net (code "61") (name "Net-(USB1-D+)") (class "Default")
      (node (ref "U7") (pin "3") (pinfunction "IO2_3") (pintype "passive"))
      (node (ref "USB1") (pin "3") (pinfunction "D+_3") (pintype "passive"))
    )
    (net (code "62") (name "Net-(USB1-D-)") (class "Default")
      (node (ref "U7") (pin "1") (pinfunction "IO1_1") (pintype "passive"))
      (node (ref "USB1") (pin "2") (pinfunction "D-_2") (pintype "passive"))
    )
    (net (code "63") (name "Net-(USB1-ID)") (class "Default")
      (node (ref "R4") (pin "2") (pintype "passive"))
      (node (ref "USB1") (pin "4") (pinfunction "ID_4") (pintype "passive"))
    )
    (net (code "64") (name "V3.3") (class "Default")
      (node (ref "C10") (pin "1") (pintype "passive"))
      (node (ref "C4") (pin "1") (pintype "passive"))
      (node (ref "C5") (pin "1") (pintype "passive"))
      (node (ref "C6") (pin "1") (pintype "passive"))
      (node (ref "C7") (pin "1") (pintype "passive"))
      (node (ref "C8") (pin "1") (pintype "passive"))
      (node (ref "C9") (pin "1") (pintype "passive"))
      (node (ref "J2") (pin "4") (pintype "passive"))
      (node (ref "J5") (pin "1") (pinfunction "Vcc_1") (pintype "passive"))
      (node (ref "Q1") (pin "1") (pintype "passive"))
      (node (ref "Q2") (pin "2") (pintype "passive"))
      (node (ref "Q3") (pin "1") (pintype "passive"))
      (node (ref "Q4") (pin "1") (pintype "passive"))
      (node (ref "R1") (pin "2") (pintype "passive"))
      (node (ref "R15") (pin "2") (pintype "passive"))
      (node (ref "R17") (pin "2") (pintype "passive"))
      (node (ref "R8") (pin "2") (pintype "passive"))
      (node (ref "R9") (pin "2") (pintype "passive"))
      (node (ref "U2") (pin "5") (pinfunction "Vout_5") (pintype "passive"))
      (node (ref "U8") (pin "17") (pinfunction "VDDIO_17") (pintype "passive"))
      (node (ref "U8") (pin "36") (pinfunction "VDDIO_36") (pintype "passive"))
      (node (ref "U8") (pin "44") (pinfunction "VDDIN_44") (pintype "passive"))
      (node (ref "U8") (pin "6") (pinfunction "VDDANA_6") (pintype "passive"))
      (node (ref "j1") (pin "2") (pinfunction "2_2") (pintype "passive"))
    )
    (net (code "65") (name "unconnected-(J5-GNDDetect-Pad9)") (class "Default")
      (node (ref "J5") (pin "9") (pinfunction "GNDDetect_9") (pintype "passive"))
    )
    (net (code "66") (name "unconnected-(J5-NC-Pad7)") (class "Default")
      (node (ref "J5") (pin "7") (pinfunction "NC_7") (pintype "passive"))
    )
    (net (code "67") (name "unconnected-(J5-NC{slash}TDI-Pad8)") (class "Default")
      (node (ref "J5") (pin "8") (pinfunction "NC/TDI_8") (pintype "passive"))
    )
    (net (code "68") (name "unconnected-(U6-A-Pad7)") (class "Default")
      (node (ref "U6") (pin "7") (pinfunction "A_7") (pintype "passive"))
    )
    (net (code "69") (name "unconnected-(U6-B-Pad6)") (class "Default")
      (node (ref "U6") (pin "6") (pinfunction "B_6") (pintype "passive"))
    )
    (net (code "70") (name "unconnected-(U6-I{slash}PWM-Pad14)") (class "Default")
      (node (ref "U6") (pin "14") (pinfunction "I/PWM_14") (pintype "passive"))
    )
    (net (code "71") (name "unconnected-(U6-U-Pad10)") (class "Default")
      (node (ref "U6") (pin "10") (pinfunction "U_10") (pintype "passive"))
    )
    (net (code "72") (name "unconnected-(U6-V-Pad9)") (class "Default")
      (node (ref "U6") (pin "9") (pinfunction "V_9") (pintype "passive"))
    )
    (net (code "73") (name "unconnected-(U6-W{slash}PWM-Pad8)") (class "Default")
      (node (ref "U6") (pin "8") (pinfunction "W/PWM_8") (pintype "passive"))
    )
  )
)
